# USB.net
KiCad netlist of a schematic drawn in Altium Designer
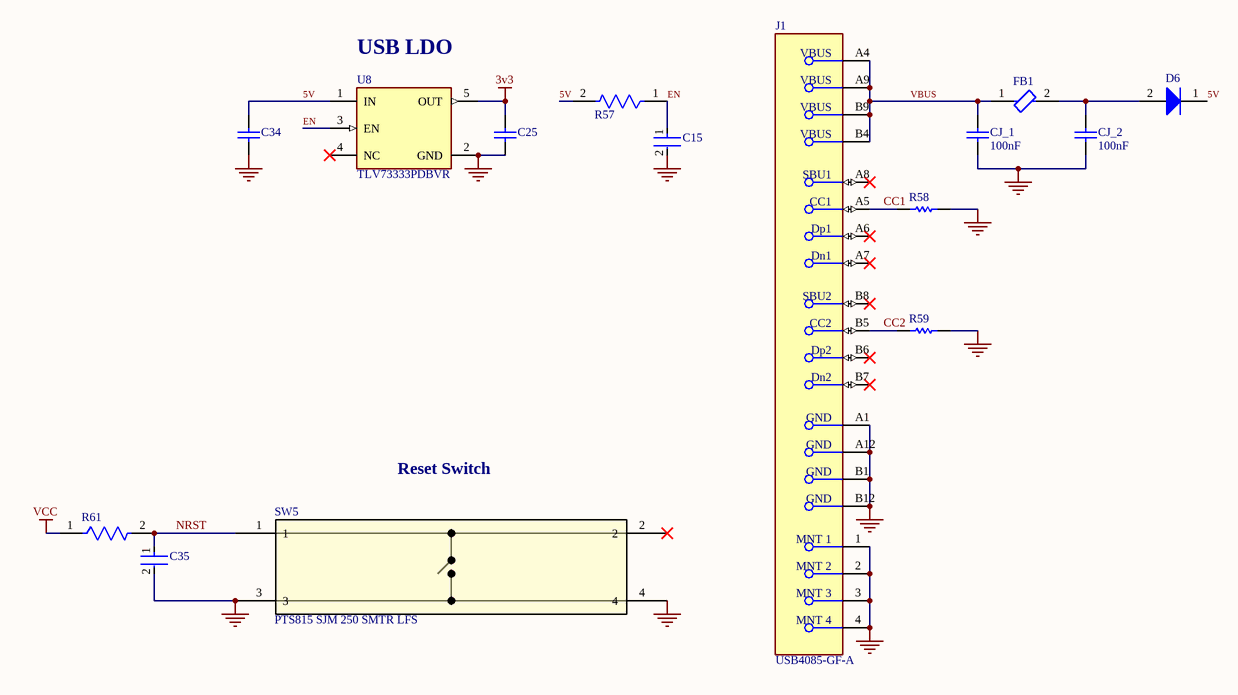
[diagram p0: USB.SchDoc]

(export (version "E")
  (design (tool "Eeschema 10.0.6"))
  (components
    (comp (ref "C15")
      (value "CC0603KRX5R8BB105")
      (footprint "FP-CC0603-DA-MFG")
      (description "CC0603 1 uF X5R 10.00% 25 V")
      (fields (field (name "OCTOPART") "https://octopart.com/cc0603krx5r8bb105-yageo-9292811"))
      (libsource (lib "Altium Content Vault") (part "11868f565c42a9108669ba33697ecf6"))
    )
    (comp (ref "C25")
      (value "C0603C105K9PACTU")
      (footprint "CAPC1608X90X35LL15T15")
      (fields (field (name "MANUFACTURER") "Kemet"))
      (libsource (lib "Altium Content Vault") (part "CAP"))
    )
    (comp (ref "C34")
      (value "C0603C105K9PACTU")
      (footprint "CAPC1608X90X35LL15T15")
      (fields (field (name "MANUFACTURER") "Kemet"))
      (libsource (lib "Altium Content Vault") (part "CAP"))
    )
    (comp (ref "C35")
      (value "CC0603KRX7R9BB104")
      (footprint "FP-CC0603-DA-MFG")
      (description "CAP CER 0.1UF 50V X7R 0603")
      (fields (field (name "MANUFACTURER") "YAGEO") (field (name "VOLTAGE") "50 V"))
      (libsource (lib "Altium Content Vault") (part "11868f565c42a9108669ba33697ecf6"))
    )
    (comp (ref "CJ_1")
      (value "100nF")
      (footprint "CAPC1206(3216)170_L")
      (description "CAP 100nF 25V ±5% 1206 (3216 Metric) Thickness 1.7mm SMD")
      (fields (field (name "TOLERANCE") "Â±5%"))
      (libsource (lib "Altium Content Vault") (part "CAP"))
    )
    (comp (ref "CJ_2")
      (value "100nF")
      (footprint "CAPC1206(3216)170_L")
      (description "CAP 100nF 25V ±5% 1206 (3216 Metric) Thickness 1.7mm SMD")
      (fields (field (name "TOLERANCE") "Â±5%"))
      (libsource (lib "Altium Content Vault") (part "CAP"))
    )
    (comp (ref "D6")
      (value "NSR0320MW2T1G")
      (footprint "ONSC-SOD-323-2-477-02_V")
      (description "Schottky Barrier Diode, 2-Pin SOD-323, Pb-Free, Tape and Reel")
      (fields (field (name "MANUFACTURER") "On Semiconductor"))
      (libsource (lib "Altium Content Vault") (part "ONSC-D-K1A2-2"))
    )
    (comp (ref "FB1")
      (value "BLM18KG601SN1D")
      (footprint "FP-BLM18-0_15-t0_8-IPC_A")
      (description "Chip Ferrite Bead, 0603, 600Ω @ 100MHz, 0.15Ω, 25%, 1.3A")
      (fields (field (name "TOLERANCE") "25%"))
      (libsource (lib "Altium Content Vault") (part "5f30dd21d616792df468990f7003faa"))
    )
    (comp (ref "J1")
      (value "USB4085-GF-A")
      (footprint "FP-USB4085-GF-A-MFG")
      (description "CONN RCPT USB2.0 TYPE C 24POS RA")
      (libsource (lib "Altium Content Vault") (part "10fa745527c8b974685cbca3c197132"))
    )
    (comp (ref "R57")
      (value "RC0603FR-0710KL")
      (footprint "FP-RC0603-0_55-IPC_C")
      (description "RES 10K OHM 1% 1/10W 0603")
      (fields (field (name "TOLERANCE") "1%"))
      (libsource (lib "Altium Content Vault") (part "1029c3af85768c4190bb7ad29bc67b5"))
    )
    (comp (ref "R58")
      (value "RC0603FR-075K1L")
      (footprint "RESC1608X55X25ML10T15")
      (fields (field (name "MANUFACTURER") "Yageo"))
      (libsource (lib "Altium Content Vault") (part "RES"))
    )
    (comp (ref "R59")
      (value "RC0603FR-075K1L")
      (footprint "RESC1608X55X25ML10T15")
      (fields (field (name "MANUFACTURER") "Yageo"))
      (libsource (lib "Altium Content Vault") (part "RES"))
    )
    (comp (ref "R61")
      (value "AC0603JR-0747KL")
      (footprint "FP-AC0603-IPC_A")
      (description "RES 47kΩ 5.00% 0.1W 0603")
      (fields (field (name "TOLERANCE") "5%"))
      (libsource (lib "Altium Content Vault") (part "1029c3af85768c4190bb7ad29bc67b5"))
    )
    (comp (ref "SW5")
      (value "PTS815 SJM 250 SMTR LFS")
      (footprint "SW4_PTS815 SJM 250 SMTR LFS_CNK")
      (description "No Description Available")
      (fields (field (name "COPYRIGHT") "Copyright (C) 2026 Ultra Librarian. All rights reserved."))
      (libsource (lib "PTS815SJM250SMTRLFS") (part "PTS815 SJM 250 SMTR LFS"))
    )
    (comp (ref "U8")
      (value "TLV73333PDBVR")
      (footprint "FP-DBV0005A-MFG")
      (description "IC REG LINEAR 3.3V 300MA SOT23-5")
      (fields
        (field (name "MANUFACTURER") "Texas Instruments")
        (field (name "OCTOPART") "https://octopart.com/tlv73333pdbvr-texas+instruments-51080890")
      )
      (libsource (lib "Altium Content Vault") (part "10cdd6a861ce8db355dac0efc8b397e"))
    )
  )
  (nets
    (net (code "1") (name "/5V") (class "Default")
      (node (ref "C34") (pin "2") (pinfunction "2_2") (pintype "passive"))
      (node (ref "D6") (pin "1") (pinfunction "K_1") (pintype "passive"))
      (node (ref "R57") (pin "2") (pinfunction "2_2") (pintype "passive"))
      (node (ref "U8") (pin "1") (pinfunction "IN_1") (pintype "power_in"))
    )
    (net (code "2") (name "/CC1") (class "Default")
      (node (ref "J1") (pin "A5") (pinfunction "CC1_A5") (pintype "bidirectional"))
      (node (ref "R58") (pin "1") (pinfunction "1_1") (pintype "passive"))
    )
    (net (code "3") (name "/CC2") (class "Default")
      (node (ref "J1") (pin "B5") (pinfunction "CC2_B5") (pintype "bidirectional"))
      (node (ref "R59") (pin "1") (pinfunction "1_1") (pintype "passive"))
    )
    (net (code "4") (name "/EN") (class "Default")
      (node (ref "C15") (pin "1") (pinfunction "1_1") (pintype "passive"))
      (node (ref "R57") (pin "1") (pinfunction "1_1") (pintype "passive"))
      (node (ref "U8") (pin "3") (pinfunction "EN_3") (pintype "input"))
    )
    (net (code "5") (name "/NRST") (class "Default")
      (node (ref "C35") (pin "1") (pinfunction "1_1") (pintype "passive"))
      (node (ref "R61") (pin "2") (pinfunction "2_2") (pintype "passive"))
      (node (ref "SW5") (pin "1") (pinfunction "1_1") (pintype "passive"))
    )
    (net (code "6") (name "/VBUS") (class "Default")
      (node (ref "CJ_1") (pin "2") (pinfunction "2_2") (pintype "passive"))
      (node (ref "FB1") (pin "1") (pinfunction "1_1") (pintype "passive"))
      (node (ref "J1") (pin "A4") (pinfunction "VBUS_A4") (pintype "power_in"))
      (node (ref "J1") (pin "A9") (pinfunction "VBUS_A9") (pintype "power_in"))
      (node (ref "J1") (pin "B4") (pinfunction "VBUS_B4") (pintype "power_in"))
      (node (ref "J1") (pin "B9") (pinfunction "VBUS_B9") (pintype "power_in"))
    )
    (net (code "7") (name "3v3") (class "Default")
      (node (ref "C25") (pin "2") (pinfunction "2_2") (pintype "passive"))
      (node (ref "U8") (pin "5") (pinfunction "OUT_5") (pintype "output"))
    )
    (net (code "8") (name "GND") (class "Default")
      (node (ref "C15") (pin "2") (pinfunction "2_2") (pintype "passive"))
      (node (ref "C25") (pin "1") (pinfunction "1_1") (pintype "passive"))
      (node (ref "C34") (pin "1") (pinfunction "1_1") (pintype "passive"))
      (node (ref "C35") (pin "2") (pinfunction "2_2") (pintype "passive"))
      (node (ref "CJ_1") (pin "1") (pinfunction "1_1") (pintype "passive"))
      (node (ref "CJ_2") (pin "1") (pinfunction "1_1") (pintype "passive"))
      (node (ref "J1") (pin "1") (pinfunction "MNT_1_1") (pintype "passive"))
      (node (ref "J1") (pin "2") (pinfunction "MNT_2_2") (pintype "passive"))
      (node (ref "J1") (pin "3") (pinfunction "MNT_3_3") (pintype "passive"))
      (node (ref "J1") (pin "4") (pinfunction "MNT_4_4") (pintype "passive"))
      (node (ref "J1") (pin "A1") (pinfunction "GND_A1") (pintype "power_in"))
      (node (ref "J1") (pin "A12") (pinfunction "GND_A12") (pintype "power_in"))
      (node (ref "J1") (pin "B1") (pinfunction "GND_B1") (pintype "power_in"))
      (node (ref "J1") (pin "B12") (pinfunction "GND_B12") (pintype "power_in"))
      (node (ref "R58") (pin "2") (pinfunction "2_2") (pintype "passive"))
      (node (ref "R59") (pin "2") (pinfunction "2_2") (pintype "passive"))
      (node (ref "SW5") (pin "3") (pinfunction "3_3") (pintype "passive"))
      (node (ref "SW5") (pin "4") (pinfunction "4_4") (pintype "passive"))
      (node (ref "U8") (pin "2") (pinfunction "GND_2") (pintype "power_in"))
    )
    (net (code "9") (name "Net-(D6-A)") (class "Default")
      (node (ref "CJ_2") (pin "2") (pinfunction "2_2") (pintype "passive"))
      (node (ref "D6") (pin "2") (pinfunction "A_2") (pintype "passive"))
      (node (ref "FB1") (pin "2") (pinfunction "2_2") (pintype "passive"))
    )
    (net (code "10") (name "VCC") (class "Default")
      (node (ref "R61") (pin "1") (pinfunction "1_1") (pintype "passive"))
    )
    (net (code "11") (name "unconnected-(J1-Dn1-PadA7)") (class "Default")
      (node (ref "J1") (pin "A7") (pinfunction "Dn1_A7") (pintype "bidirectional+no_connect"))
    )
    (net (code "12") (name "unconnected-(J1-Dn2-PadB7)") (class "Default")
      (node (ref "J1") (pin "B7") (pinfunction "Dn2_B7") (pintype "bidirectional+no_connect"))
    )
    (net (code "13") (name "unconnected-(J1-Dp1-PadA6)") (class "Default")
      (node (ref "J1") (pin "A6") (pinfunction "Dp1_A6") (pintype "bidirectional+no_connect"))
    )
    (net (code "14") (name "unconnected-(J1-Dp2-PadB6)") (class "Default")
      (node (ref "J1") (pin "B6") (pinfunction "Dp2_B6") (pintype "bidirectional+no_connect"))
    )
    (net (code "15") (name "unconnected-(J1-SBU1-PadA8)") (class "Default")
      (node (ref "J1") (pin "A8") (pinfunction "SBU1_A8") (pintype "bidirectional+no_connect"))
    )
    (net (code "16") (name "unconnected-(J1-SBU2-PadB8)") (class "Default")
      (node (ref "J1") (pin "B8") (pinfunction "SBU2_B8") (pintype "bidirectional+no_connect"))
    )
    (net (code "17") (name "unconnected-(SW5-Pad2)") (class "Default")
      (node (ref "SW5") (pin "2") (pinfunction "2_2") (pintype "passive+no_connect"))
    )
    (net (code "18") (name "unconnected-(U8-NC-Pad4)") (class "Default")
      (node (ref "U8") (pin "4") (pinfunction "NC_4") (pintype "passive+no_connect"))
    )
  )
)
